# S7CAS-PLEIADES-CARTE-MERE_P06_POWER1.net
KiCad netlist of a schematic drawn in Altium Designer
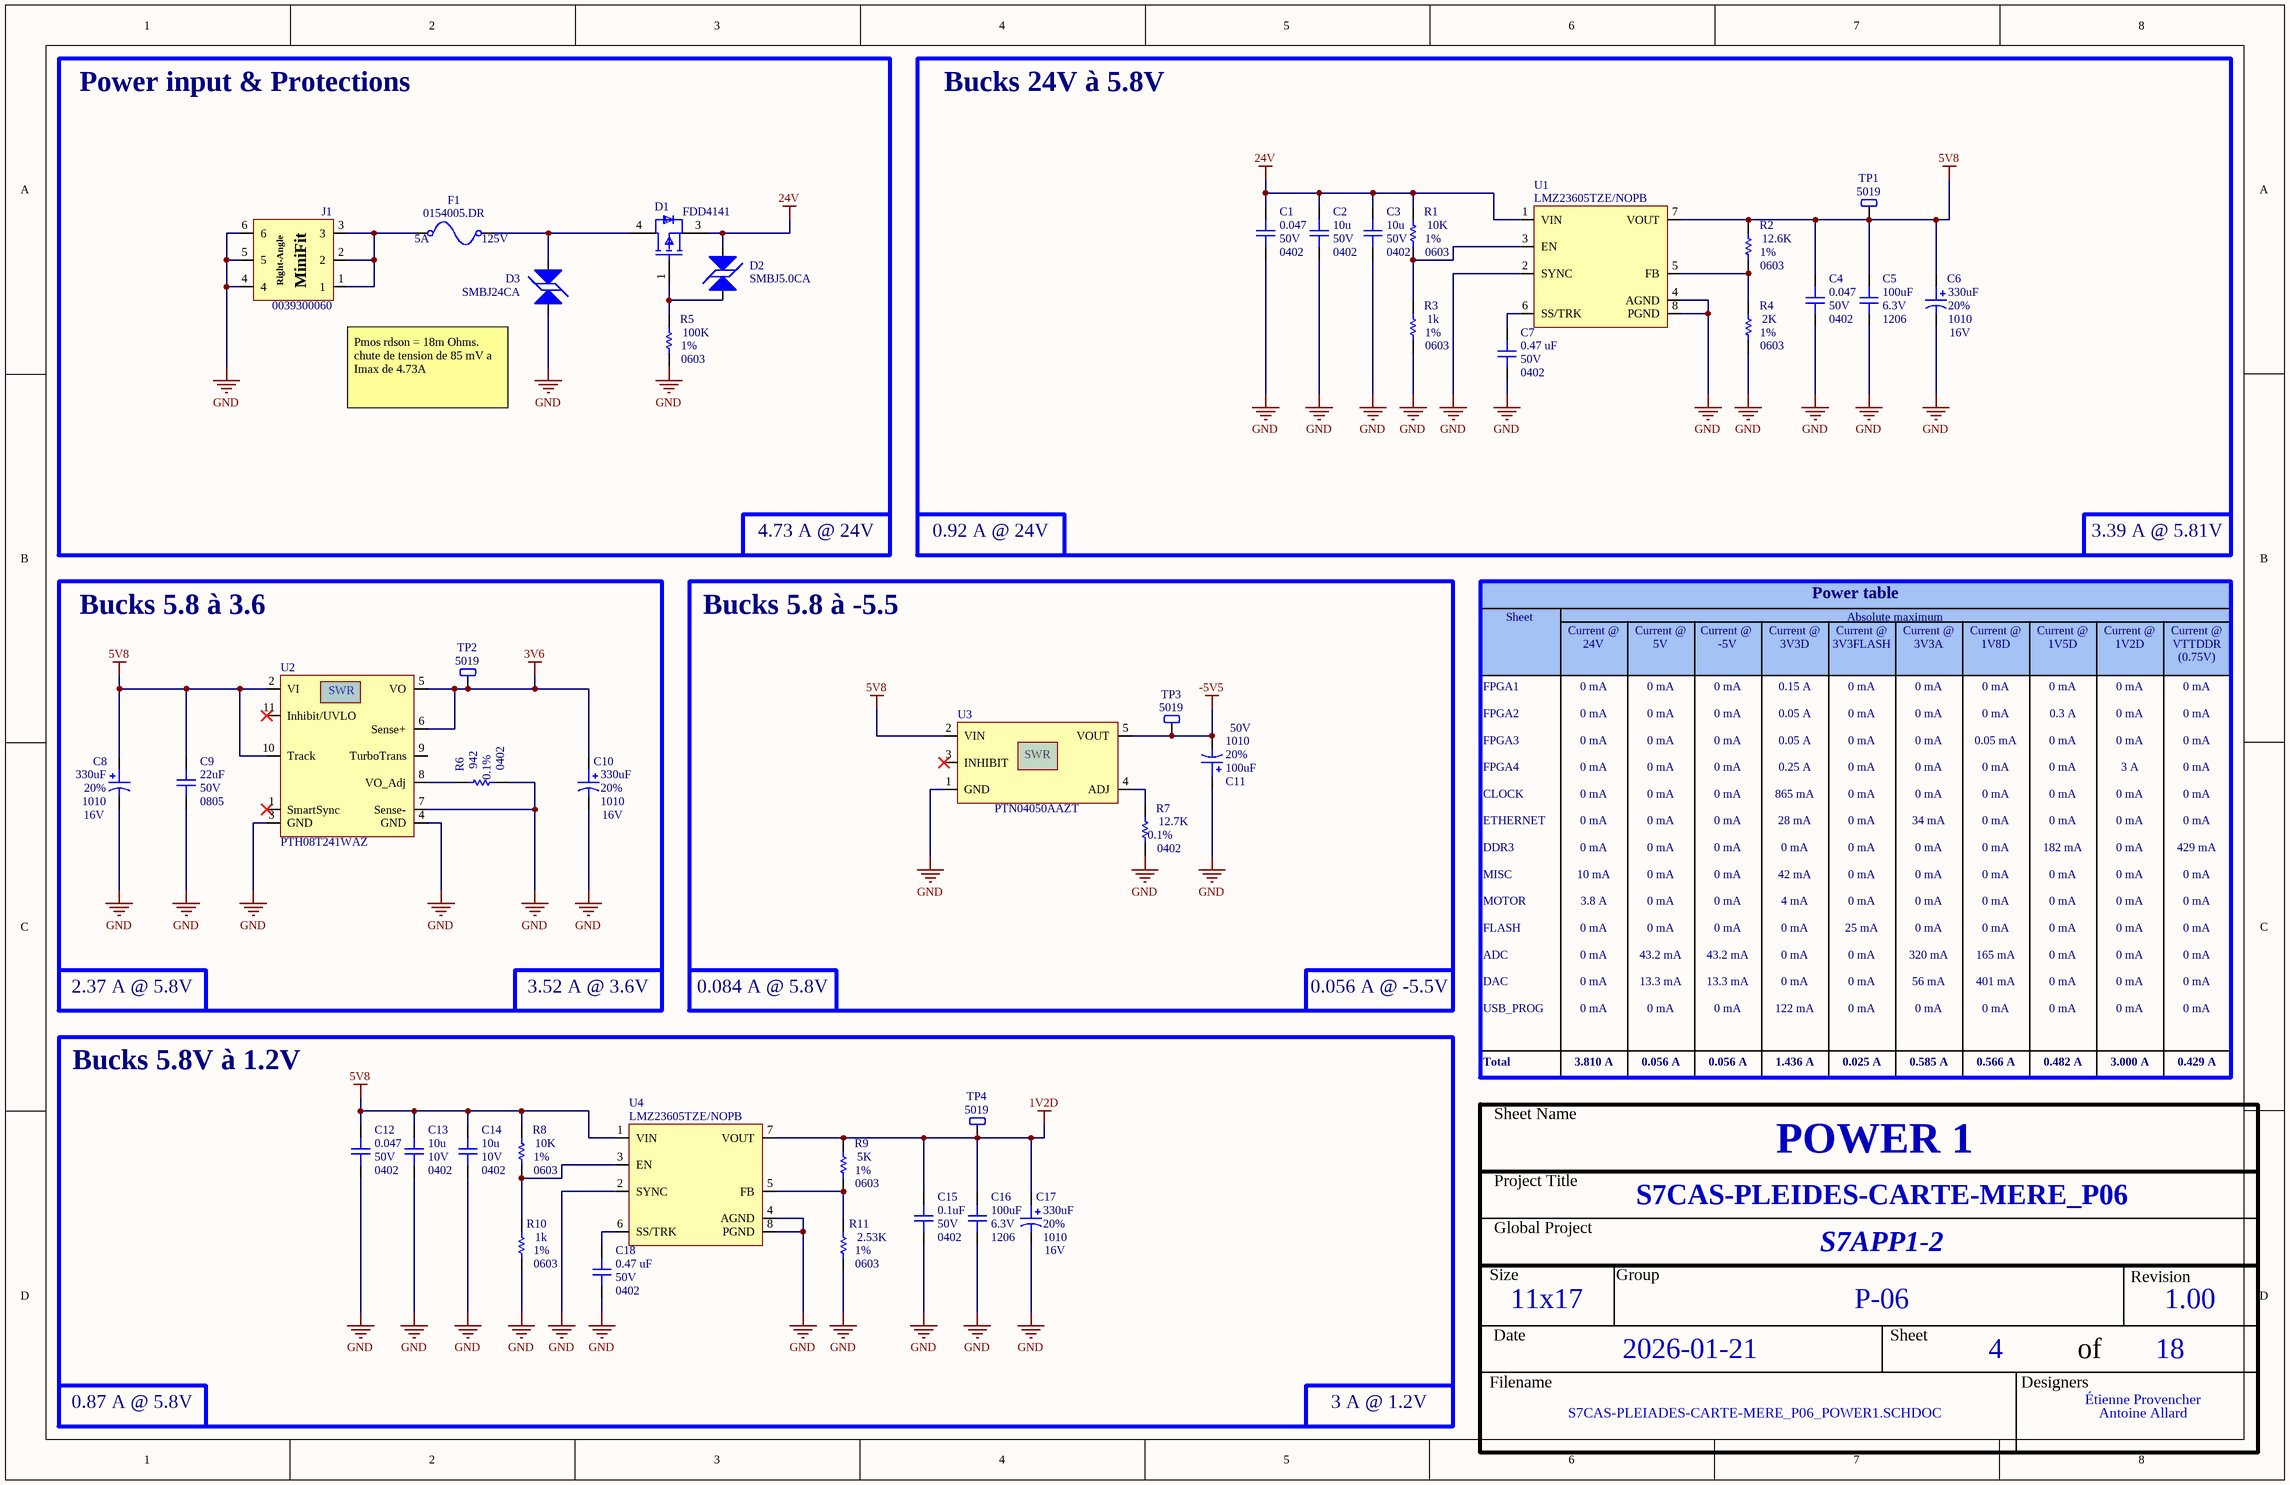
[diagram p0: S7CAS-PLEIADES-CARTE-MERE_P06_POWER1.SCHDOC]

(export (version "E")
  (design (tool "Eeschema 10.0.6"))
  (components
    (comp (ref "C1")
      (value "0.047")
      (footprint "CAP_0402")
      (description "CAP - 0402")
      (fields
        (field (name "VOLTAGE") "50V")
        (field (name "PACKAGE") "0402")
        (field (name "CREATEDBY") "Jonathan Bouchard")
      )
      (libsource (lib "s7cas_lib2023") (part "CAP - 0402"))
    )
    (comp (ref "C2")
      (value "10u")
      (footprint "CAP_0402")
      (description "CAP - 0402")
      (fields
        (field (name "VOLTAGE") "50V")
        (field (name "PACKAGE") "0402")
        (field (name "CREATEDBY") "Jonathan Bouchard")
      )
      (libsource (lib "s7cas_lib2023") (part "CAP - 0402"))
    )
    (comp (ref "C3")
      (value "10u")
      (footprint "CAP_0402")
      (description "CAP - 0402")
      (fields
        (field (name "VOLTAGE") "50V")
        (field (name "PACKAGE") "0402")
        (field (name "CREATEDBY") "Jonathan Bouchard")
      )
      (libsource (lib "s7cas_lib2023") (part "CAP - 0402"))
    )
    (comp (ref "C4")
      (value "0.047")
      (footprint "CAP_0402")
      (description "CAP - 0402")
      (fields
        (field (name "VOLTAGE") "50V")
        (field (name "PACKAGE") "0402")
        (field (name "CREATEDBY") "Jonathan Bouchard")
      )
      (libsource (lib "s7cas_lib2023") (part "CAP - 0402"))
    )
    (comp (ref "C5")
      (value "100uF")
      (footprint "CAP_1206")
      (description "CAP - 1206")
      (fields
        (field (name "VOLTAGE") "6.3V")
        (field (name "PACKAGE") "1206")
        (field (name "CREATEDBY") "Jonathan Bouchard")
      )
      (libsource (lib "s7cas_lib2023") (part "CAP - 1206"))
    )
    (comp (ref "C6")
      (value "330uF")
      (footprint "CAP_ALU_1010_vishay")
      (description "CAP - ALU 330uF 20% 16V - 1010")
      (fields
        (field (name "MFG") "Vishay Dale")
        (field (name "MFG PART NUMBER") "MAL214699501E3")
        (field (name "VOLTAGE") "16V")
        (field (name "PACKAGE") "1010")
        (field (name "PRECISION") "20%")
        (field (name "CREATEDBY") "Jonathan Bouchard")
      )
      (libsource (lib "s7cas_lib2023") (part "CAP_ALU_MAL214699501E3"))
    )
    (comp (ref "C7")
      (value "0.47 uF")
      (footprint "CAP_0402")
      (description "CAP - 0402")
      (fields
        (field (name "VOLTAGE") "50V")
        (field (name "PACKAGE") "0402")
        (field (name "CREATEDBY") "Jonathan Bouchard")
      )
      (libsource (lib "s7cas_lib2023") (part "CAP - 0402"))
    )
    (comp (ref "C8")
      (value "330uF")
      (footprint "CAP_ALU_1010_vishay")
      (description "CAP - ALU 330uF 20% 16V - 1010")
      (fields
        (field (name "MFG") "Vishay Dale")
        (field (name "MFG PART NUMBER") "MAL214699501E3")
        (field (name "VOLTAGE") "16V")
        (field (name "PACKAGE") "1010")
        (field (name "PRECISION") "20%")
        (field (name "CREATEDBY") "Jonathan Bouchard")
      )
      (libsource (lib "") (part "CAP_ALU_MAL214699501E3_1"))
    )
    (comp (ref "C9")
      (value "22uF")
      (footprint "CAP_0805")
      (description "CAP - 0805")
      (fields
        (field (name "VOLTAGE") "50V")
        (field (name "PACKAGE") "0805")
        (field (name "CREATEDBY") "Jonathan Bouchard")
      )
      (libsource (lib "s7cas_lib2023") (part "CAP - 0805"))
    )
    (comp (ref "C10")
      (value "330uF")
      (footprint "CAP_ALU_1010_vishay")
      (description "CAP - ALU 330uF 20% 16V - 1010")
      (fields
        (field (name "MFG") "Vishay Dale")
        (field (name "MFG PART NUMBER") "MAL214699501E3")
        (field (name "VOLTAGE") "16V")
        (field (name "PACKAGE") "1010")
        (field (name "PRECISION") "20%")
        (field (name "CREATEDBY") "Jonathan Bouchard")
      )
      (libsource (lib "s7cas_lib2023") (part "CAP_ALU_MAL214699501E3"))
    )
    (comp (ref "C11")
      (value "100uF")
      (footprint "CAP_ALU_1010_vishay")
      (description "CAP - ALU 100uF 20% 50V - 1010")
      (fields
        (field (name "MFG") "Vishay Dale")
        (field (name "MFG PART NUMBER") "MAL215099101E3")
        (field (name "VOLTAGE") "50V")
        (field (name "PACKAGE") "1010")
        (field (name "PRECISION") "20%")
        (field (name "CREATEDBY") "Jonathan Bouchard")
      )
      (libsource (lib "s7cas_lib2023") (part "CAP_ALU_MAL215099101E3"))
    )
    (comp (ref "C12")
      (value "0.047")
      (footprint "CAP_0402")
      (description "CAP - 0402")
      (fields
        (field (name "VOLTAGE") "50V")
        (field (name "PACKAGE") "0402")
        (field (name "CREATEDBY") "Jonathan Bouchard")
      )
      (libsource (lib "s7cas_lib2023") (part "CAP - 0402"))
    )
    (comp (ref "C13")
      (value "10u")
      (footprint "CAP_0402")
      (description "CAP - 0402")
      (fields
        (field (name "VOLTAGE") "10V")
        (field (name "PACKAGE") "0402")
        (field (name "CREATEDBY") "Jonathan Bouchard")
      )
      (libsource (lib "s7cas_lib2023") (part "CAP - 0402"))
    )
    (comp (ref "C14")
      (value "10u")
      (footprint "CAP_0402")
      (description "CAP - 0402")
      (fields
        (field (name "VOLTAGE") "10V")
        (field (name "PACKAGE") "0402")
        (field (name "CREATEDBY") "Jonathan Bouchard")
      )
      (libsource (lib "s7cas_lib2023") (part "CAP - 0402"))
    )
    (comp (ref "C15")
      (value "0.1uF")
      (footprint "CAP_0402")
      (description "CAP - 0402")
      (fields
        (field (name "VOLTAGE") "50V")
        (field (name "PACKAGE") "0402")
        (field (name "CREATEDBY") "Jonathan Bouchard")
      )
      (libsource (lib "s7cas_lib2023") (part "CAP - 0402"))
    )
    (comp (ref "C16")
      (value "100uF")
      (footprint "CAP_1206")
      (description "CAP - 1206")
      (fields
        (field (name "VOLTAGE") "6.3V")
        (field (name "PACKAGE") "1206")
        (field (name "CREATEDBY") "Jonathan Bouchard")
      )
      (libsource (lib "s7cas_lib2023") (part "CAP - 1206"))
    )
    (comp (ref "C17")
      (value "330uF")
      (footprint "CAP_ALU_1010_vishay")
      (description "CAP - ALU 330uF 20% 16V - 1010")
      (fields
        (field (name "MFG") "Vishay Dale")
        (field (name "MFG PART NUMBER") "MAL214699501E3")
        (field (name "VOLTAGE") "16V")
        (field (name "PACKAGE") "1010")
        (field (name "PRECISION") "20%")
        (field (name "CREATEDBY") "Jonathan Bouchard")
      )
      (libsource (lib "s7cas_lib2023") (part "CAP_ALU_MAL214699501E3"))
    )
    (comp (ref "C18")
      (value "0.47 uF")
      (footprint "CAP_0402")
      (description "CAP - 0402")
      (fields
        (field (name "VOLTAGE") "50V")
        (field (name "PACKAGE") "0402")
        (field (name "CREATEDBY") "Jonathan Bouchard")
      )
      (libsource (lib "s7cas_lib2023") (part "CAP - 0402"))
    )
    (comp (ref "D1")
      (value "FDD4141")
      (footprint "FP-369AS-MFG")
      (description "MOSFET P-CH 40V 10.8A DPAK")
      (fields
        (field (name "OCTOPART") "https://octopart.com/fdd4141-on+semiconductor-84325802")
        (field (name "MANUFACTURER") "ON Semiconductor")
      )
      (libsource (lib "Altium Content Vault") (part "ec195c925100855187fe8c06440c3e1"))
    )
    (comp (ref "D2")
      (value "SMBJ5.0CA")
      (footprint "TVS_PWR_SMBJ5.0CA")
      (description "TVS - BIDIR 5V 9.2V 600W - DO214AA")
      (fields
        (field (name "CREATEDBY/DATE") "Jonathan Bouchard - 2019-03-22")
        (field (name "VERIFIEDBY") "Nicolas V. (2019-05-06)")
      )
      (libsource (lib "s7cas_lib2023") (part "TVS_PWR_SMBJ5.0CA"))
    )
    (comp (ref "D3")
      (value "SMBJ24CA")
      (footprint "TVS_PWR_SMBJ36CA")
      (description "TVS - 24V 26.7V 600W - DO214AA")
      (fields
        (field (name "CREATEDBY/DATE") "Arnaud Samson - 06/07/18")
        (field (name "VERIFIEDBY") "Jonathan Bouchard - 2018-07-13")
      )
      (libsource (lib "s7cas_lib2023") (part "TVS_PWR_SMBJ24CA"))
    )
    (comp (ref "F1")
      (value "0154005.DR")
      (footprint "FUS_0154XXX.DR")
      (description "FUS - 5 A 125 VAC/VDC - 2-SMD")
      (fields
        (field (name "VOLTAGE RATING") "125V")
        (field (name "CURRENT RATING") "5A")
        (field (name "CREATEDBY/DATE") "Arnaud Samson - 06/07/18")
        (field (name "VERIFIEDBY") "Jonathan Bouchard 2018-07-16")
      )
      (libsource (lib "s7cas_lib2023") (part "FUS_0154005.DR"))
    )
    (comp (ref "J1")
      (value "0039300060")
      (footprint "CON_MINIFIT_0039300060")
      (description "CON - Mini-Fit Through Hole, Right Angle 6 position")
      (fields
        (field (name "CREATEDBY/DATE") "Joel Lemay 2018-06-21")
        (field (name "VERIFIEDBY") "Caroline Paulin - 10 sept 2018")
      )
      (libsource (lib "s7cas_lib2023") (part "CON_MINIFIT_0039300060"))
    )
    (comp (ref "R1")
      (value "10K")
      (footprint "RES_0603")
      (description "RES - 0603")
      (fields
        (field (name "PACKAGE") "0603")
        (field (name "PRECISION") "1%")
        (field (name "CREATEDBY") "Jonathan Bouchard")
      )
      (libsource (lib "s7cas_lib2023") (part "RES - 0603"))
    )
    (comp (ref "R2")
      (value "12.6K")
      (footprint "RES_0603")
      (description "RES - 0603")
      (fields
        (field (name "PACKAGE") "0603")
        (field (name "PRECISION") "1%")
        (field (name "CREATEDBY") "Jonathan Bouchard")
      )
      (libsource (lib "s7cas_lib2023") (part "RES - 0603"))
    )
    (comp (ref "R3")
      (value "1k")
      (footprint "RES_0603")
      (description "RES - 0603")
      (fields
        (field (name "PACKAGE") "0603")
        (field (name "PRECISION") "1%")
        (field (name "CREATEDBY") "Jonathan Bouchard")
      )
      (libsource (lib "s7cas_lib2023") (part "RES - 0603"))
    )
    (comp (ref "R4")
      (value "2K")
      (footprint "RES_0603")
      (description "RES - 0603")
      (fields
        (field (name "PACKAGE") "0603")
        (field (name "PRECISION") "1%")
        (field (name "CREATEDBY") "Jonathan Bouchard")
      )
      (libsource (lib "s7cas_lib2023") (part "RES - 0603"))
    )
    (comp (ref "R5")
      (value "100K")
      (footprint "RES_0603")
      (description "RES - 0603")
      (fields
        (field (name "PACKAGE") "0603")
        (field (name "PRECISION") "1%")
        (field (name "CREATEDBY") "Jonathan Bouchard")
      )
      (libsource (lib "s7cas_lib2023") (part "RES - 0603"))
    )
    (comp (ref "R6")
      (value "942")
      (footprint "RES_0402")
      (description "RES - 0402")
      (fields
        (field (name "VOLTAGE") "50V")
        (field (name "POWER") "1/16W")
        (field (name "PACKAGE") "0402")
        (field (name "PRECISION") "0.1%")
        (field (name "CREATEDBY") "Jonathan Bouchard")
      )
      (libsource (lib "s7cas_lib2023") (part "RES - 0402"))
    )
    (comp (ref "R7")
      (value "12.7K")
      (footprint "RES_0402")
      (description "RES - 0402")
      (fields
        (field (name "VOLTAGE") "50V")
        (field (name "POWER") "1/16W")
        (field (name "PACKAGE") "0402")
        (field (name "PRECISION") "0.1%")
        (field (name "CREATEDBY") "Jonathan Bouchard")
      )
      (libsource (lib "s7cas_lib2023") (part "RES - 0402"))
    )
    (comp (ref "R8")
      (value "10K")
      (footprint "RES_0603")
      (description "RES - 0603")
      (fields
        (field (name "PACKAGE") "0603")
        (field (name "PRECISION") "1%")
        (field (name "CREATEDBY") "Jonathan Bouchard")
      )
      (libsource (lib "s7cas_lib2023") (part "RES - 0603"))
    )
    (comp (ref "R9")
      (value "5K")
      (footprint "RES_0603")
      (description "RES - 0603")
      (fields
        (field (name "PACKAGE") "0603")
        (field (name "PRECISION") "1%")
        (field (name "CREATEDBY") "Jonathan Bouchard")
      )
      (libsource (lib "s7cas_lib2023") (part "RES - 0603"))
    )
    (comp (ref "R10")
      (value "1k")
      (footprint "RES_0603")
      (description "RES - 0603")
      (fields
        (field (name "PACKAGE") "0603")
        (field (name "PRECISION") "1%")
        (field (name "CREATEDBY") "Jonathan Bouchard")
      )
      (libsource (lib "s7cas_lib2023") (part "RES - 0603"))
    )
    (comp (ref "R11")
      (value "2.53K")
      (footprint "RES_0603")
      (description "RES - 0603")
      (fields
        (field (name "PACKAGE") "0603")
        (field (name "PRECISION") "1%")
        (field (name "CREATEDBY") "Jonathan Bouchard")
      )
      (libsource (lib "s7cas_lib2023") (part "RES - 0603"))
    )
    (comp (ref "TP1")
      (value "5019")
      (footprint "TPO_SMD_5019")
      (description "TPO - PC TEST POINT MINI - SMD")
      (fields
        (field (name "CREATEDBY/DATE") "Olivier Bernard / 5/12/2017")
        (field (name "VERIFIEDBY") "Caroline Paulin / 5 juillet 2018")
      )
      (libsource (lib "s7cas_lib2023") (part "TPO_SMD_5019"))
    )
    (comp (ref "TP2")
      (value "5019")
      (footprint "TPO_SMD_5019")
      (description "TPO - PC TEST POINT MINI - SMD")
      (fields
        (field (name "CREATEDBY/DATE") "Olivier Bernard / 5/12/2017")
        (field (name "VERIFIEDBY") "Caroline Paulin / 5 juillet 2018")
      )
      (libsource (lib "s7cas_lib2023") (part "TPO_SMD_5019"))
    )
    (comp (ref "TP3")
      (value "5019")
      (footprint "TPO_SMD_5019")
      (description "TPO - PC TEST POINT MINI - SMD")
      (fields
        (field (name "CREATEDBY/DATE") "Olivier Bernard / 5/12/2017")
        (field (name "VERIFIEDBY") "Caroline Paulin / 5 juillet 2018")
      )
      (libsource (lib "s7cas_lib2023") (part "TPO_SMD_5019"))
    )
    (comp (ref "TP4")
      (value "5019")
      (footprint "TPO_SMD_5019")
      (description "TPO - PC TEST POINT MINI - SMD")
      (fields
        (field (name "CREATEDBY/DATE") "Olivier Bernard / 5/12/2017")
        (field (name "VERIFIEDBY") "Caroline Paulin / 5 juillet 2018")
      )
      (libsource (lib "s7cas_lib2023") (part "TPO_SMD_5019"))
    )
    (comp (ref "U1")
      (value "LMZ23605TZE/NOPB")
      (footprint "REG_SWR_LMZ23605TZE/NOPB")
      (description "REG - IC BUCK SYNC 36V 5A - TO-PMOD-7")
      (fields
        (field (name "CREATEDBY/DATE") "Arnaud Samson - 05/07/18")
        (field (name "VERIFIEDBY") "Jonathan Bouchard 2018-07-13")
      )
      (libsource (lib "s7cas_lib2023") (part "REG_SWR_LMZ23605TZE/NOPB"))
    )
    (comp (ref "U2")
      (value "PTH08T241WAZ")
      (footprint "REG_SWR_PTH08T241WAZ")
      (description "REG - MODULE PIP 10A 14VIN - 11-SMD")
      (fields
        (field (name "CREATEDBY/DATE") "Olivier Bernard / 6/5/2018")
        (field (name "VERIFIEDBY") "Caroline Paulin / 10 juillet 2018")
      )
      (libsource (lib "s7cas_lib2023") (part "REG_SWR_PTH08T241WAZ"))
    )
    (comp (ref "U3")
      (value "PTN04050AAZT")
      (footprint "REG_SWR_PTN04050AAZT")
      (description "REG - SWR -15 ~ -3.3V 1A 6W - 5-SMD")
      (fields
        (field (name "CREATEDBY/DATE") "Ihsane Najahi 2019-09-25")
        (field (name "VERIFIEDBY") "C.Paulin (9-10-2019)")
      )
      (libsource (lib "s7cas_lib2023") (part "REG_SWR_PTN04050AAZT"))
    )
    (comp (ref "U4")
      (value "LMZ23605TZE/NOPB")
      (footprint "REG_SWR_LMZ23605TZE/NOPB")
      (description "REG - IC BUCK SYNC 36V 5A - TO-PMOD-7")
      (fields
        (field (name "CREATEDBY/DATE") "Arnaud Samson - 05/07/18")
        (field (name "VERIFIEDBY") "Jonathan Bouchard 2018-07-13")
      )
      (libsource (lib "s7cas_lib2023") (part "REG_SWR_LMZ23605TZE/NOPB"))
    )
  )
  (nets
    (net (code "1") (name "-5V5") (class "Default")
      (node (ref "C11") (pin "2") (pinfunction "2_2") (pintype "passive"))
      (node (ref "TP3") (pin "1") (pinfunction "1_1") (pintype "passive"))
      (node (ref "U3") (pin "5") (pinfunction "VOUT_5") (pintype "passive"))
    )
    (net (code "2") (name "1V2D") (class "Default")
      (node (ref "C15") (pin "2") (pinfunction "2_2") (pintype "passive"))
      (node (ref "C16") (pin "2") (pinfunction "2_2") (pintype "passive"))
      (node (ref "C17") (pin "1") (pinfunction "1_1") (pintype "passive"))
      (node (ref "R9") (pin "2") (pinfunction "2_2") (pintype "passive"))
      (node (ref "TP4") (pin "1") (pinfunction "1_1") (pintype "passive"))
      (node (ref "U4") (pin "7") (pinfunction "VOUT_7") (pintype "passive"))
    )
    (net (code "3") (name "3V6") (class "Default")
      (node (ref "C10") (pin "1") (pinfunction "1_1") (pintype "passive"))
      (node (ref "TP2") (pin "1") (pinfunction "1_1") (pintype "passive"))
      (node (ref "U2") (pin "5") (pinfunction "VO_5") (pintype "passive"))
      (node (ref "U2") (pin "6") (pinfunction "Sense+_6") (pintype "passive"))
    )
    (net (code "4") (name "5V8") (class "Default")
      (node (ref "C12") (pin "2") (pinfunction "2_2") (pintype "passive"))
      (node (ref "C13") (pin "2") (pinfunction "2_2") (pintype "passive"))
      (node (ref "C14") (pin "2") (pinfunction "2_2") (pintype "passive"))
      (node (ref "C4") (pin "2") (pinfunction "2_2") (pintype "passive"))
      (node (ref "C5") (pin "2") (pinfunction "2_2") (pintype "passive"))
      (node (ref "C6") (pin "1") (pinfunction "1_1") (pintype "passive"))
      (node (ref "C8") (pin "1") (pinfunction "1_1") (pintype "passive"))
      (node (ref "C9") (pin "2") (pinfunction "2_2") (pintype "passive"))
      (node (ref "R2") (pin "2") (pinfunction "2_2") (pintype "passive"))
      (node (ref "R8") (pin "2") (pinfunction "2_2") (pintype "passive"))
      (node (ref "TP1") (pin "1") (pinfunction "1_1") (pintype "passive"))
      (node (ref "U1") (pin "7") (pinfunction "VOUT_7") (pintype "passive"))
      (node (ref "U2") (pin "10") (pinfunction "Track_10") (pintype "passive"))
      (node (ref "U2") (pin "2") (pinfunction "VI_2") (pintype "passive"))
      (node (ref "U3") (pin "2") (pinfunction "VIN_2") (pintype "passive"))
      (node (ref "U4") (pin "1") (pinfunction "VIN_1") (pintype "passive"))
    )
    (net (code "5") (name "24V") (class "Default")
      (node (ref "C1") (pin "2") (pinfunction "2_2") (pintype "passive"))
      (node (ref "C2") (pin "2") (pinfunction "2_2") (pintype "passive"))
      (node (ref "C3") (pin "2") (pinfunction "2_2") (pintype "passive"))
      (node (ref "D1") (pin "3") (pinfunction "S_3") (pintype "passive"))
      (node (ref "D2") (pin "1") (pinfunction "1_1") (pintype "passive"))
      (node (ref "R1") (pin "2") (pinfunction "2_2") (pintype "passive"))
      (node (ref "U1") (pin "1") (pinfunction "VIN_1") (pintype "passive"))
    )
    (net (code "6") (name "GND") (class "Default")
      (node (ref "C1") (pin "1") (pinfunction "1_1") (pintype "passive"))
      (node (ref "C10") (pin "2") (pinfunction "2_2") (pintype "passive"))
      (node (ref "C11") (pin "1") (pinfunction "1_1") (pintype "passive"))
      (node (ref "C12") (pin "1") (pinfunction "1_1") (pintype "passive"))
      (node (ref "C13") (pin "1") (pinfunction "1_1") (pintype "passive"))
      (node (ref "C14") (pin "1") (pinfunction "1_1") (pintype "passive"))
      (node (ref "C15") (pin "1") (pinfunction "1_1") (pintype "passive"))
      (node (ref "C16") (pin "1") (pinfunction "1_1") (pintype "passive"))
      (node (ref "C17") (pin "2") (pinfunction "2_2") (pintype "passive"))
      (node (ref "C18") (pin "1") (pinfunction "1_1") (pintype "passive"))
      (node (ref "C2") (pin "1") (pinfunction "1_1") (pintype "passive"))
      (node (ref "C3") (pin "1") (pinfunction "1_1") (pintype "passive"))
      (node (ref "C4") (pin "1") (pinfunction "1_1") (pintype "passive"))
      (node (ref "C5") (pin "1") (pinfunction "1_1") (pintype "passive"))
      (node (ref "C6") (pin "2") (pinfunction "2_2") (pintype "passive"))
      (node (ref "C7") (pin "1") (pinfunction "1_1") (pintype "passive"))
      (node (ref "C8") (pin "2") (pinfunction "2_2") (pintype "passive"))
      (node (ref "C9") (pin "1") (pinfunction "1_1") (pintype "passive"))
      (node (ref "D3") (pin "2") (pinfunction "2_2") (pintype "passive"))
      (node (ref "J1") (pin "4") (pinfunction "4_4") (pintype "passive"))
      (node (ref "J1") (pin "5") (pinfunction "5_5") (pintype "passive"))
      (node (ref "J1") (pin "6") (pinfunction "6_6") (pintype "passive"))
      (node (ref "R10") (pin "1") (pinfunction "1_1") (pintype "passive"))
      (node (ref "R11") (pin "1") (pinfunction "1_1") (pintype "passive"))
      (node (ref "R3") (pin "1") (pinfunction "1_1") (pintype "passive"))
      (node (ref "R4") (pin "1") (pinfunction "1_1") (pintype "passive"))
      (node (ref "R5") (pin "1") (pinfunction "1_1") (pintype "passive"))
      (node (ref "R6") (pin "1") (pinfunction "1_1") (pintype "passive"))
      (node (ref "R7") (pin "1") (pinfunction "1_1") (pintype "passive"))
      (node (ref "U1") (pin "2") (pinfunction "SYNC_2") (pintype "passive"))
      (node (ref "U1") (pin "4") (pinfunction "AGND_4") (pintype "passive"))
      (node (ref "U1") (pin "8") (pinfunction "PGND_8") (pintype "passive"))
      (node (ref "U2") (pin "3") (pinfunction "GND_3") (pintype "passive"))
      (node (ref "U2") (pin "4") (pinfunction "GND_4") (pintype "passive"))
      (node (ref "U2") (pin "7") (pinfunction "Sense-_7") (pintype "passive"))
      (node (ref "U3") (pin "1") (pinfunction "GND_1") (pintype "passive"))
      (node (ref "U4") (pin "2") (pinfunction "SYNC_2") (pintype "passive"))
      (node (ref "U4") (pin "4") (pinfunction "AGND_4") (pintype "passive"))
      (node (ref "U4") (pin "8") (pinfunction "PGND_8") (pintype "passive"))
    )
    (net (code "7") (name "Net-(D1-D)") (class "Default")
      (node (ref "D1") (pin "4") (pinfunction "D_4") (pintype "passive"))
      (node (ref "D3") (pin "1") (pinfunction "1_1") (pintype "passive"))
      (node (ref "F1") (pin "2") (pinfunction "2_2") (pintype "passive"))
    )
    (net (code "8") (name "Net-(D1-G)") (class "Default")
      (node (ref "D1") (pin "1") (pinfunction "G_1") (pintype "passive"))
      (node (ref "D2") (pin "2") (pinfunction "2_2") (pintype "passive"))
      (node (ref "R5") (pin "2") (pinfunction "2_2") (pintype "passive"))
    )
    (net (code "9") (name "Net-(F1-Pad1)") (class "Default")
      (node (ref "F1") (pin "1") (pinfunction "1_1") (pintype "passive"))
      (node (ref "J1") (pin "1") (pinfunction "1_1") (pintype "passive"))
      (node (ref "J1") (pin "2") (pinfunction "2_2") (pintype "passive"))
      (node (ref "J1") (pin "3") (pinfunction "3_3") (pintype "passive"))
    )
    (net (code "10") (name "Net-(U1-EN)") (class "Default")
      (node (ref "R1") (pin "1") (pinfunction "1_1") (pintype "passive"))
      (node (ref "R3") (pin "2") (pinfunction "2_2") (pintype "passive"))
      (node (ref "U1") (pin "3") (pinfunction "EN_3") (pintype "passive"))
    )
    (net (code "11") (name "Net-(U1-FB)") (class "Default")
      (node (ref "R2") (pin "1") (pinfunction "1_1") (pintype "passive"))
      (node (ref "R4") (pin "2") (pinfunction "2_2") (pintype "passive"))
      (node (ref "U1") (pin "5") (pinfunction "FB_5") (pintype "passive"))
    )
    (net (code "12") (name "Net-(U1-SS{slash}TRK)") (class "Default")
      (node (ref "C7") (pin "2") (pinfunction "2_2") (pintype "passive"))
      (node (ref "U1") (pin "6") (pinfunction "SS/TRK_6") (pintype "passive"))
    )
    (net (code "13") (name "Net-(U2-VO_Adj)") (class "Default")
      (node (ref "R6") (pin "2") (pinfunction "2_2") (pintype "passive"))
      (node (ref "U2") (pin "8") (pinfunction "VO_Adj_8") (pintype "passive"))
    )
    (net (code "14") (name "Net-(U3-ADJ)") (class "Default")
      (node (ref "R7") (pin "2") (pinfunction "2_2") (pintype "passive"))
      (node (ref "U3") (pin "4") (pinfunction "ADJ_4") (pintype "passive"))
    )
    (net (code "15") (name "Net-(U4-EN)") (class "Default")
      (node (ref "R10") (pin "2") (pinfunction "2_2") (pintype "passive"))
      (node (ref "R8") (pin "1") (pinfunction "1_1") (pintype "passive"))
      (node (ref "U4") (pin "3") (pinfunction "EN_3") (pintype "passive"))
    )
    (net (code "16") (name "Net-(U4-FB)") (class "Default")
      (node (ref "R11") (pin "2") (pinfunction "2_2") (pintype "passive"))
      (node (ref "R9") (pin "1") (pinfunction "1_1") (pintype "passive"))
      (node (ref "U4") (pin "5") (pinfunction "FB_5") (pintype "passive"))
    )
    (net (code "17") (name "Net-(U4-SS{slash}TRK)") (class "Default")
      (node (ref "C18") (pin "2") (pinfunction "2_2") (pintype "passive"))
      (node (ref "U4") (pin "6") (pinfunction "SS/TRK_6") (pintype "passive"))
    )
    (net (code "18") (name "unconnected-(U2-Inhibit{slash}UVLO-Pad11)") (class "Default")
      (node (ref "U2") (pin "11") (pinfunction "Inhibit/UVLO_11") (pintype "passive+no_connect"))
    )
    (net (code "19") (name "unconnected-(U2-SmartSync-Pad1)") (class "Default")
      (node (ref "U2") (pin "1") (pinfunction "SmartSync_1") (pintype "passive+no_connect"))
    )
    (net (code "20") (name "unconnected-(U2-TurboTrans-Pad9)") (class "Default")
      (node (ref "U2") (pin "9") (pinfunction "TurboTrans_9") (pintype "passive"))
    )
    (net (code "21") (name "unconnected-(U3-INHIBIT-Pad3)") (class "Default")
      (node (ref "U3") (pin "3") (pinfunction "INHIBIT_3") (pintype "passive+no_connect"))
    )
  )
)
